# his_masters_noise.net
KiCad netlist of a schematic drawn in EAGLE
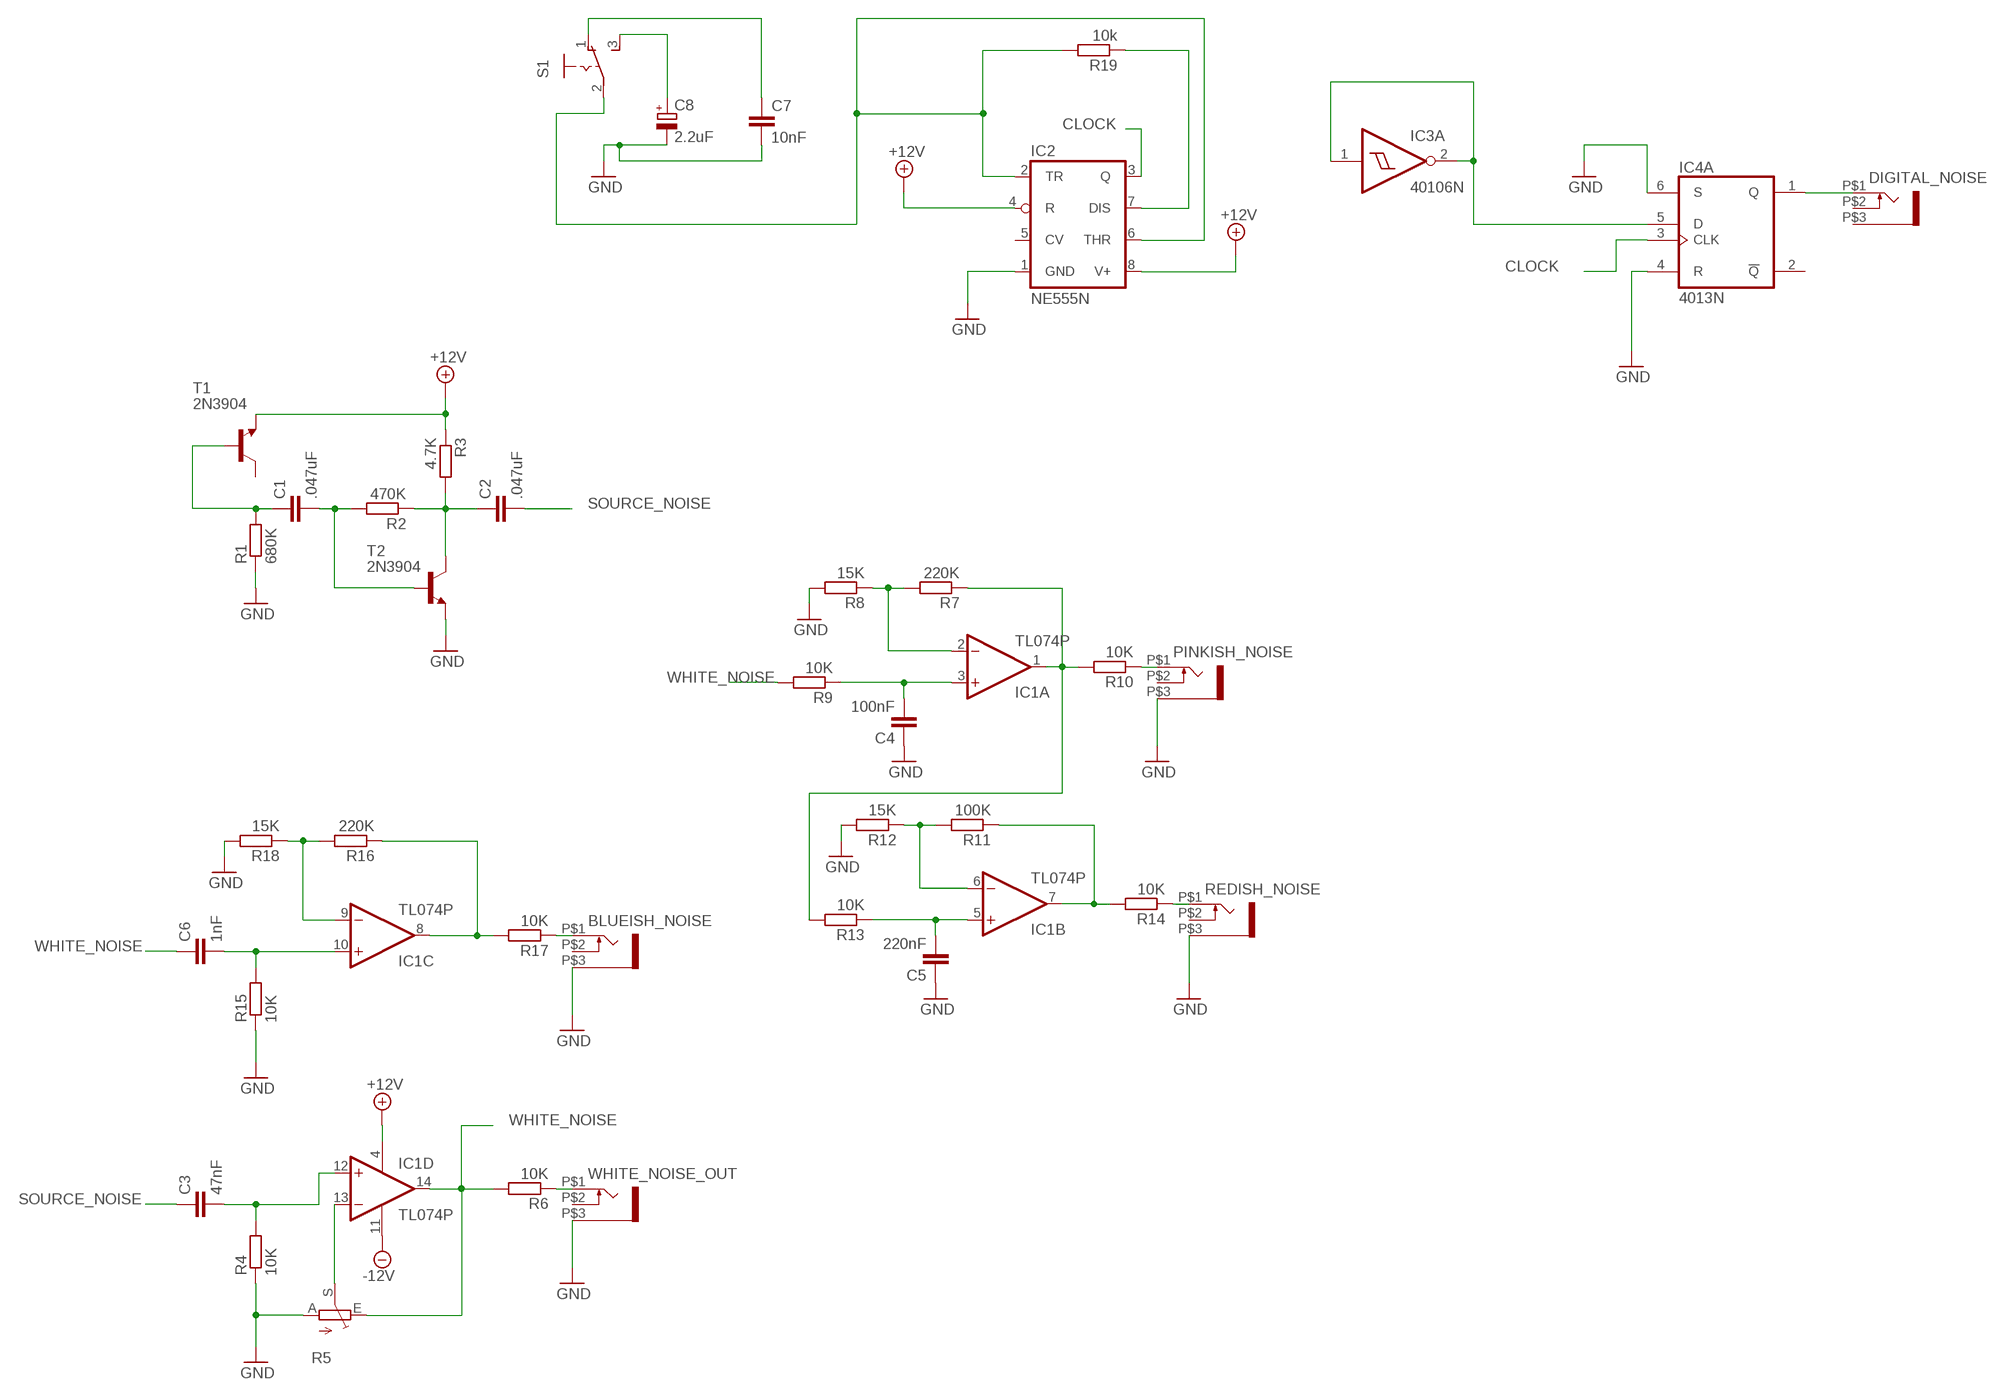
[diagram p0: schematic, sheet 1]

(export (version "E")
  (design (tool "Eeschema 10.0.6"))
  (components
    (comp (ref "BLUEISH_NOISE")
      (value "WQP-PJ301M-12_JACK")
      (footprint "eagle-import:WQP-PJ301M-12_JACK")
      (libsource (lib "eagle-import") (part "WQP-PJ301M-12_JACK"))
    )
    (comp (ref "C1")
      (value ".047uF")
      (footprint "eagle-import:C025-030X050")
      (libsource (lib "eagle-import") (part "C-EU025-030X050"))
    )
    (comp (ref "C2")
      (value ".047uF")
      (footprint "eagle-import:C025-030X050")
      (libsource (lib "eagle-import") (part "C-EU025-030X050"))
    )
    (comp (ref "C3")
      (value "47nF")
      (footprint "eagle-import:C025-030X050")
      (libsource (lib "eagle-import") (part "C-EU025-030X050"))
    )
    (comp (ref "C4")
      (value "100nF")
      (footprint "eagle-import:C025-030X050")
      (libsource (lib "eagle-import") (part "C-EU025-030X050"))
    )
    (comp (ref "C5")
      (value "220nF")
      (footprint "eagle-import:C025-030X050")
      (libsource (lib "eagle-import") (part "C-EU025-030X050"))
    )
    (comp (ref "C6")
      (value "1nF")
      (footprint "eagle-import:C025-030X050")
      (libsource (lib "eagle-import") (part "C-EU025-030X050"))
    )
    (comp (ref "C7")
      (value "10nF")
      (footprint "eagle-import:C025-025X050")
      (libsource (lib "eagle-import") (part "C-EU025-025X050"))
    )
    (comp (ref "C8")
      (value "2.2uF")
      (footprint "eagle-import:E1,8-4")
      (libsource (lib "eagle-import") (part "CPOL-EUE1.8-4"))
    )
    (comp (ref "DIGITAL_NOISE")
      (value "WQP-PJ301M-12_JACK")
      (footprint "eagle-import:WQP-PJ301M-12_JACK")
      (libsource (lib "eagle-import") (part "WQP-PJ301M-12_JACK"))
    )
    (comp (ref "IC1")
      (value "TL074P")
      (footprint "eagle-import:DIL14")
      (libsource (lib "eagle-import") (part "TL074P"))
    )
    (comp (ref "IC2")
      (value "NE555N")
      (footprint "eagle-import:DIL08")
      (libsource (lib "eagle-import") (part "555NNE"))
    )
    (comp (ref "IC3")
      (value "40106N")
      (footprint "eagle-import:DIL14")
      (libsource (lib "eagle-import") (part "40106N"))
    )
    (comp (ref "IC4")
      (value "4013N")
      (footprint "eagle-import:DIL14")
      (libsource (lib "eagle-import") (part "4013N"))
    )
    (comp (ref "PINKISH_NOISE")
      (value "WQP-PJ301M-12_JACK")
      (footprint "eagle-import:WQP-PJ301M-12_JACK")
      (libsource (lib "eagle-import") (part "WQP-PJ301M-12_JACK"))
    )
    (comp (ref "R1")
      (value "680K")
      (footprint "eagle-import:0204_7")
      (libsource (lib "eagle-import") (part "R-EU_0204/7"))
    )
    (comp (ref "R2")
      (value "470K")
      (footprint "eagle-import:0204_7")
      (libsource (lib "eagle-import") (part "R-EU_0204/7"))
    )
    (comp (ref "R3")
      (value "4.7K")
      (footprint "eagle-import:0204_7")
      (libsource (lib "eagle-import") (part "R-EU_0204/7"))
    )
    (comp (ref "R4")
      (value "10K")
      (footprint "eagle-import:0204_7")
      (libsource (lib "eagle-import") (part "R-EU_0204/7"))
    )
    (comp (ref "R5")
      (value "TRIM_EU-S64W")
      (footprint "eagle-import:S64W")
      (libsource (lib "eagle-import") (part "TRIM_EU-S64W"))
    )
    (comp (ref "R6")
      (value "10K")
      (footprint "eagle-import:0204_7")
      (libsource (lib "eagle-import") (part "R-EU_0204/7"))
    )
    (comp (ref "R7")
      (value "220K")
      (footprint "eagle-import:0204_7")
      (libsource (lib "eagle-import") (part "R-EU_0204/7"))
    )
    (comp (ref "R8")
      (value "15K")
      (footprint "eagle-import:0204_7")
      (libsource (lib "eagle-import") (part "R-EU_0204/7"))
    )
    (comp (ref "R9")
      (value "10K")
      (footprint "eagle-import:0204_7")
      (libsource (lib "eagle-import") (part "R-EU_0204/7"))
    )
    (comp (ref "R10")
      (value "10K")
      (footprint "eagle-import:0204_7")
      (libsource (lib "eagle-import") (part "R-EU_0204/7"))
    )
    (comp (ref "R11")
      (value "100K")
      (footprint "eagle-import:0204_7")
      (libsource (lib "eagle-import") (part "R-EU_0204/7"))
    )
    (comp (ref "R12")
      (value "15K")
      (footprint "eagle-import:0204_7")
      (libsource (lib "eagle-import") (part "R-EU_0204/7"))
    )
    (comp (ref "R13")
      (value "10K")
      (footprint "eagle-import:0204_7")
      (libsource (lib "eagle-import") (part "R-EU_0204/7"))
    )
    (comp (ref "R14")
      (value "10K")
      (footprint "eagle-import:0204_7")
      (libsource (lib "eagle-import") (part "R-EU_0204/7"))
    )
    (comp (ref "R15")
      (value "10K")
      (footprint "eagle-import:0204_7")
      (libsource (lib "eagle-import") (part "R-EU_0204/7"))
    )
    (comp (ref "R16")
      (value "220K")
      (footprint "eagle-import:0204_7")
      (libsource (lib "eagle-import") (part "R-EU_0204/7"))
    )
    (comp (ref "R17")
      (value "10K")
      (footprint "eagle-import:0204_7")
      (libsource (lib "eagle-import") (part "R-EU_0204/7"))
    )
    (comp (ref "R18")
      (value "15K")
      (footprint "eagle-import:0204_7")
      (libsource (lib "eagle-import") (part "R-EU_0204/7"))
    )
    (comp (ref "R19")
      (value "10k")
      (footprint "eagle-import:0204_7")
      (libsource (lib "eagle-import") (part "R-EU_0204/7"))
    )
    (comp (ref "REDISH_NOISE")
      (value "WQP-PJ301M-12_JACK")
      (footprint "eagle-import:WQP-PJ301M-12_JACK")
      (libsource (lib "eagle-import") (part "WQP-PJ301M-12_JACK"))
    )
    (comp (ref "S1")
      (value "255SB")
      (footprint "eagle-import:255SB")
      (libsource (lib "eagle-import") (part "255SB"))
    )
    (comp (ref "T1")
      (value "2N3904")
      (footprint "eagle-import:TO92")
      (libsource (lib "eagle-import") (part "2N3904"))
    )
    (comp (ref "T2")
      (value "2N3904")
      (footprint "eagle-import:TO92")
      (libsource (lib "eagle-import") (part "2N3904"))
    )
    (comp (ref "WHITE_NOISE_OUT")
      (value "WQP-PJ301M-12_JACK")
      (footprint "eagle-import:WQP-PJ301M-12_JACK")
      (libsource (lib "eagle-import") (part "WQP-PJ301M-12_JACK"))
    )
  )
  (nets
    (net (code "1") (name "+12V") (class "Default")
      (node (ref "IC1") (pin "4") (pinfunction "V+_4") (pintype "power_in"))
      (node (ref "IC2") (pin "4") (pinfunction "R_4") (pintype "input"))
      (node (ref "IC2") (pin "8") (pinfunction "V+_8") (pintype "power_in"))
      (node (ref "R3") (pin "1") (pinfunction "1_1") (pintype "passive"))
      (node (ref "T1") (pin "3") (pinfunction "E_3") (pintype "passive"))
    )
    (net (code "2") (name "-12V") (class "Default")
      (node (ref "IC1") (pin "11") (pinfunction "V-_11") (pintype "power_in"))
    )
    (net (code "3") (name "/CLOCK") (class "Default")
      (node (ref "IC2") (pin "3") (pinfunction "Q_3") (pintype "output"))
      (node (ref "IC4") (pin "3") (pinfunction "CLK_3") (pintype "input"))
    )
    (net (code "4") (name "/SOURCE_NOISE") (class "Default")
      (node (ref "C2") (pin "2") (pinfunction "2_2") (pintype "passive"))
      (node (ref "C3") (pin "1") (pinfunction "1_1") (pintype "passive"))
    )
    (net (code "5") (name "/WHITE_NOISE") (class "Default")
      (node (ref "C6") (pin "1") (pinfunction "1_1") (pintype "passive"))
      (node (ref "IC1") (pin "14") (pinfunction "OUT_14") (pintype "output"))
      (node (ref "IC1") (pin "8") (pinfunction "OUT_8") (pintype "output"))
      (node (ref "R16") (pin "1") (pinfunction "1_1") (pintype "passive"))
      (node (ref "R17") (pin "2") (pinfunction "2_2") (pintype "passive"))
      (node (ref "R5") (pin "E") (pinfunction "E_E") (pintype "passive"))
      (node (ref "R6") (pin "2") (pinfunction "2_2") (pintype "passive"))
      (node (ref "R9") (pin "2") (pinfunction "2_2") (pintype "passive"))
    )
    (net (code "6") (name "GND") (class "Default")
      (node (ref "BLUEISH_NOISE") (pin "P$3") (pinfunction "1_P$3") (pintype "passive"))
      (node (ref "C4") (pin "1") (pinfunction "1_1") (pintype "passive"))
      (node (ref "C5") (pin "1") (pinfunction "1_1") (pintype "passive"))
      (node (ref "C7") (pin "2") (pinfunction "2_2") (pintype "passive"))
      (node (ref "C8") (pin "-") (pinfunction "-_-") (pintype "passive"))
      (node (ref "IC2") (pin "1") (pinfunction "GND_1") (pintype "power_in"))
      (node (ref "IC4") (pin "4") (pinfunction "R_4") (pintype "input"))
      (node (ref "IC4") (pin "6") (pinfunction "S_6") (pintype "input"))
      (node (ref "PINKISH_NOISE") (pin "P$3") (pinfunction "1_P$3") (pintype "passive"))
      (node (ref "R1") (pin "1") (pinfunction "1_1") (pintype "passive"))
      (node (ref "R12") (pin "2") (pinfunction "2_2") (pintype "passive"))
      (node (ref "R15") (pin "1") (pinfunction "1_1") (pintype "passive"))
      (node (ref "R18") (pin "2") (pinfunction "2_2") (pintype "passive"))
      (node (ref "R4") (pin "1") (pinfunction "1_1") (pintype "passive"))
      (node (ref "R5") (pin "A") (pinfunction "A_A") (pintype "passive"))
      (node (ref "R8") (pin "2") (pinfunction "2_2") (pintype "passive"))
      (node (ref "REDISH_NOISE") (pin "P$3") (pinfunction "1_P$3") (pintype "passive"))
      (node (ref "T2") (pin "3") (pinfunction "E_3") (pintype "passive"))
      (node (ref "WHITE_NOISE_OUT") (pin "P$3") (pinfunction "1_P$3") (pintype "passive"))
    )
    (net (code "7") (name "Net-(BLUEISH_NOISE-2)") (class "Default")
      (node (ref "BLUEISH_NOISE") (pin "P$1") (pinfunction "2_P$1") (pintype "passive"))
      (node (ref "R17") (pin "1") (pinfunction "1_1") (pintype "passive"))
    )
    (net (code "8") (name "Net-(DIGITAL_NOISE-2)") (class "Default")
      (node (ref "DIGITAL_NOISE") (pin "P$1") (pinfunction "2_P$1") (pintype "passive"))
      (node (ref "IC4") (pin "1") (pinfunction "Q_1") (pintype "output"))
    )
    (net (code "9") (name "Net-(IC1A-+IN)") (class "Default")
      (node (ref "C4") (pin "2") (pinfunction "2_2") (pintype "passive"))
      (node (ref "IC1") (pin "3") (pinfunction "+IN_3") (pintype "input"))
      (node (ref "R9") (pin "1") (pinfunction "1_1") (pintype "passive"))
    )
    (net (code "10") (name "Net-(IC1A--IN)") (class "Default")
      (node (ref "IC1") (pin "2") (pinfunction "-IN_2") (pintype "input"))
      (node (ref "R7") (pin "2") (pinfunction "2_2") (pintype "passive"))
      (node (ref "R8") (pin "1") (pinfunction "1_1") (pintype "passive"))
    )
    (net (code "11") (name "Net-(IC1A-OUT)") (class "Default")
      (node (ref "IC1") (pin "1") (pinfunction "OUT_1") (pintype "output"))
      (node (ref "R10") (pin "2") (pinfunction "2_2") (pintype "passive"))
      (node (ref "R13") (pin "2") (pinfunction "2_2") (pintype "passive"))
      (node (ref "R7") (pin "1") (pinfunction "1_1") (pintype "passive"))
    )
    (net (code "12") (name "Net-(IC1B-+IN)") (class "Default")
      (node (ref "C5") (pin "2") (pinfunction "2_2") (pintype "passive"))
      (node (ref "IC1") (pin "5") (pinfunction "+IN_5") (pintype "input"))
      (node (ref "R13") (pin "1") (pinfunction "1_1") (pintype "passive"))
    )
    (net (code "13") (name "Net-(IC1B--IN)") (class "Default")
      (node (ref "IC1") (pin "6") (pinfunction "-IN_6") (pintype "input"))
      (node (ref "R11") (pin "2") (pinfunction "2_2") (pintype "passive"))
      (node (ref "R12") (pin "1") (pinfunction "1_1") (pintype "passive"))
    )
    (net (code "14") (name "Net-(IC1B-OUT)") (class "Default")
      (node (ref "IC1") (pin "7") (pinfunction "OUT_7") (pintype "output"))
      (node (ref "R11") (pin "1") (pinfunction "1_1") (pintype "passive"))
      (node (ref "R14") (pin "2") (pinfunction "2_2") (pintype "passive"))
    )
    (net (code "15") (name "Net-(IC1C-+IN)") (class "Default")
      (node (ref "C6") (pin "2") (pinfunction "2_2") (pintype "passive"))
      (node (ref "IC1") (pin "10") (pinfunction "+IN_10") (pintype "input"))
      (node (ref "R15") (pin "2") (pinfunction "2_2") (pintype "passive"))
    )
    (net (code "16") (name "Net-(IC1C--IN)") (class "Default")
      (node (ref "IC1") (pin "9") (pinfunction "-IN_9") (pintype "input"))
      (node (ref "R16") (pin "2") (pinfunction "2_2") (pintype "passive"))
      (node (ref "R18") (pin "1") (pinfunction "1_1") (pintype "passive"))
    )
    (net (code "17") (name "Net-(IC1D-+IN)") (class "Default")
      (node (ref "C3") (pin "2") (pinfunction "2_2") (pintype "passive"))
      (node (ref "IC1") (pin "12") (pinfunction "+IN_12") (pintype "input"))
      (node (ref "R4") (pin "2") (pinfunction "2_2") (pintype "passive"))
    )
    (net (code "18") (name "Net-(IC1D--IN)") (class "Default")
      (node (ref "IC1") (pin "13") (pinfunction "-IN_13") (pintype "input"))
      (node (ref "R5") (pin "S") (pinfunction "S_S") (pintype "passive"))
    )
    (net (code "19") (name "Net-(IC2-DIS)") (class "Default")
      (node (ref "IC2") (pin "7") (pinfunction "DIS_7") (pintype "input"))
      (node (ref "R19") (pin "1") (pinfunction "1_1") (pintype "passive"))
    )
    (net (code "20") (name "Net-(IC2-THR)") (class "Default")
      (node (ref "IC2") (pin "2") (pinfunction "TR_2") (pintype "input"))
      (node (ref "IC2") (pin "6") (pinfunction "THR_6") (pintype "input"))
      (node (ref "R19") (pin "2") (pinfunction "2_2") (pintype "passive"))
      (node (ref "S1") (pin "2") (pinfunction "P_2") (pintype "passive"))
    )
    (net (code "21") (name "Net-(IC3A-I)") (class "Default")
      (node (ref "IC3") (pin "1") (pinfunction "I_1") (pintype "input"))
      (node (ref "IC3") (pin "2") (pinfunction "O_2") (pintype "output"))
      (node (ref "IC4") (pin "5") (pinfunction "D_5") (pintype "input"))
    )
    (net (code "22") (name "Net-(PINKISH_NOISE-2)") (class "Default")
      (node (ref "PINKISH_NOISE") (pin "P$1") (pinfunction "2_P$1") (pintype "passive"))
      (node (ref "R10") (pin "1") (pinfunction "1_1") (pintype "passive"))
    )
    (net (code "23") (name "Net-(REDISH_NOISE-2)") (class "Default")
      (node (ref "R14") (pin "1") (pinfunction "1_1") (pintype "passive"))
      (node (ref "REDISH_NOISE") (pin "P$1") (pinfunction "2_P$1") (pintype "passive"))
    )
    (net (code "24") (name "Net-(S1-O)") (class "Default")
      (node (ref "C7") (pin "1") (pinfunction "1_1") (pintype "passive"))
      (node (ref "S1") (pin "1") (pinfunction "O_1") (pintype "passive"))
    )
    (net (code "25") (name "Net-(S1-S)") (class "Default")
      (node (ref "C8") (pin "+") (pinfunction "+_+") (pintype "passive"))
      (node (ref "S1") (pin "3") (pinfunction "S_3") (pintype "passive"))
    )
    (net (code "26") (name "Net-(T1-B)") (class "Default")
      (node (ref "C1") (pin "1") (pinfunction "1_1") (pintype "passive"))
      (node (ref "R1") (pin "2") (pinfunction "2_2") (pintype "passive"))
      (node (ref "T1") (pin "2") (pinfunction "B_2") (pintype "passive"))
    )
    (net (code "27") (name "Net-(T2-B)") (class "Default")
      (node (ref "C1") (pin "2") (pinfunction "2_2") (pintype "passive"))
      (node (ref "R2") (pin "2") (pinfunction "2_2") (pintype "passive"))
      (node (ref "T2") (pin "2") (pinfunction "B_2") (pintype "passive"))
    )
    (net (code "28") (name "Net-(T2-C)") (class "Default")
      (node (ref "C2") (pin "1") (pinfunction "1_1") (pintype "passive"))
      (node (ref "R2") (pin "1") (pinfunction "1_1") (pintype "passive"))
      (node (ref "R3") (pin "2") (pinfunction "2_2") (pintype "passive"))
      (node (ref "T2") (pin "1") (pinfunction "C_1") (pintype "passive"))
    )
    (net (code "29") (name "Net-(WHITE_NOISE_OUT-2)") (class "Default")
      (node (ref "R6") (pin "1") (pinfunction "1_1") (pintype "passive"))
      (node (ref "WHITE_NOISE_OUT") (pin "P$1") (pinfunction "2_P$1") (pintype "passive"))
    )
    (net (code "30") (name "unconnected-(BLUEISH_NOISE-3-PadP$2)") (class "Default")
      (node (ref "BLUEISH_NOISE") (pin "P$2") (pinfunction "3_P$2") (pintype "passive"))
    )
    (net (code "31") (name "unconnected-(DIGITAL_NOISE-1-PadP$3)") (class "Default")
      (node (ref "DIGITAL_NOISE") (pin "P$3") (pinfunction "1_P$3") (pintype "passive"))
    )
    (net (code "32") (name "unconnected-(DIGITAL_NOISE-3-PadP$2)") (class "Default")
      (node (ref "DIGITAL_NOISE") (pin "P$2") (pinfunction "3_P$2") (pintype "passive"))
    )
    (net (code "33") (name "unconnected-(IC2-CV-Pad5)") (class "Default")
      (node (ref "IC2") (pin "5") (pinfunction "CV_5") (pintype "input"))
    )
    (net (code "34") (name "unconnected-(IC4A-~{Q}-Pad2)") (class "Default")
      (node (ref "IC4") (pin "2") (pinfunction "~{Q}_2") (pintype "output"))
    )
    (net (code "35") (name "unconnected-(PINKISH_NOISE-3-PadP$2)") (class "Default")
      (node (ref "PINKISH_NOISE") (pin "P$2") (pinfunction "3_P$2") (pintype "passive"))
    )
    (net (code "36") (name "unconnected-(REDISH_NOISE-3-PadP$2)") (class "Default")
      (node (ref "REDISH_NOISE") (pin "P$2") (pinfunction "3_P$2") (pintype "passive"))
    )
    (net (code "37") (name "unconnected-(T1-C-Pad1)") (class "Default")
      (node (ref "T1") (pin "1") (pinfunction "C_1") (pintype "passive"))
    )
    (net (code "38") (name "unconnected-(WHITE_NOISE_OUT-3-PadP$2)") (class "Default")
      (node (ref "WHITE_NOISE_OUT") (pin "P$2") (pinfunction "3_P$2") (pintype "passive"))
    )
  )
)
